# Camera_driver.net
KiCad netlist of a schematic drawn in EAGLE
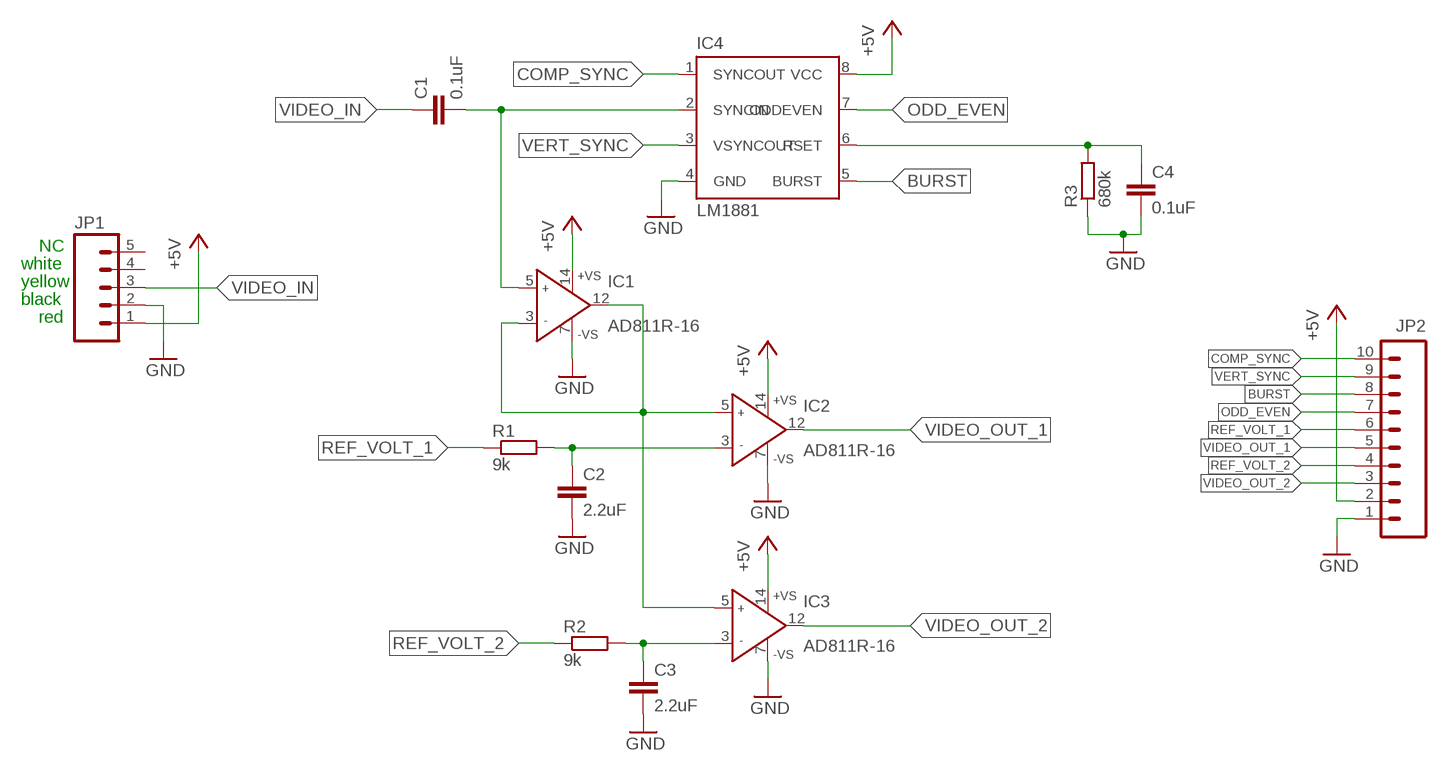
[diagram p0: schematic, sheet 1]

(export (version "E")
  (design (tool "Eeschema 10.0.6"))
  (components
    (comp (ref "C1")
      (value "0.1uF")
      (footprint "eagle-import:C0603")
      (libsource (lib "eagle-import") (part "C-EUC0603"))
    )
    (comp (ref "C2")
      (value "2.2uF")
      (footprint "eagle-import:C0603")
      (libsource (lib "eagle-import") (part "C-EUC0603"))
    )
    (comp (ref "C3")
      (value "2.2uF")
      (footprint "eagle-import:C0603")
      (libsource (lib "eagle-import") (part "C-EUC0603"))
    )
    (comp (ref "C4")
      (value "0.1uF")
      (footprint "eagle-import:C0603")
      (libsource (lib "eagle-import") (part "C-EUC0603"))
    )
    (comp (ref "IC1")
      (value "AD811R-16")
      (footprint "eagle-import:SOIC16R")
      (fields (field (name "MF") "ALTERA CORPORATION") (field (name "MPN") "AD811ARZ-16"))
      (libsource (lib "eagle-import") (part "AD811R-16"))
    )
    (comp (ref "IC2")
      (value "AD811R-16")
      (footprint "eagle-import:SOIC16R")
      (fields (field (name "MF") "ALTERA CORPORATION") (field (name "MPN") "AD811ARZ-16"))
      (libsource (lib "eagle-import") (part "AD811R-16"))
    )
    (comp (ref "IC3")
      (value "AD811R-16")
      (footprint "eagle-import:SOIC16R")
      (fields (field (name "MF") "ALTERA CORPORATION") (field (name "MPN") "AD811ARZ-16"))
      (libsource (lib "eagle-import") (part "AD811R-16"))
    )
    (comp (ref "IC4")
      (value "LM1881")
      (footprint "eagle-import:DIL08")
      (libsource (lib "eagle-import") (part "LM1881"))
    )
    (comp (ref "JP1")
      (value "M05PTH")
      (footprint "eagle-import:1X05")
      (libsource (lib "eagle-import") (part "M05PTH"))
    )
    (comp (ref "JP2")
      (value "M10SILK_FEMALE_PTH")
      (footprint "eagle-import:1X10")
      (libsource (lib "eagle-import") (part "M10SILK_FEMALE_PTH"))
    )
    (comp (ref "R1")
      (value "9k")
      (footprint "eagle-import:R0603")
      (libsource (lib "eagle-import") (part "R-EU_R0603"))
    )
    (comp (ref "R2")
      (value "9k")
      (footprint "eagle-import:R0603")
      (libsource (lib "eagle-import") (part "R-EU_R0603"))
    )
    (comp (ref "R3")
      (value "680k")
      (footprint "eagle-import:R0603")
      (libsource (lib "eagle-import") (part "R-EU_R0603"))
    )
  )
  (nets
    (net (code "1") (name "+5V") (class "Default")
      (node (ref "IC1") (pin "14") (pinfunction "+VS_14") (pintype "input"))
      (node (ref "IC2") (pin "14") (pinfunction "+VS_14") (pintype "input"))
      (node (ref "IC3") (pin "14") (pinfunction "+VS_14") (pintype "input"))
      (node (ref "IC4") (pin "8") (pinfunction "VCC_8") (pintype "power_in"))
      (node (ref "JP1") (pin "1") (pinfunction "1_1") (pintype "passive"))
      (node (ref "JP2") (pin "2") (pinfunction "2_2") (pintype "passive"))
    )
    (net (code "2") (name "BURST") (class "Default")
      (node (ref "IC4") (pin "5") (pinfunction "BURST_5") (pintype "output"))
      (node (ref "JP2") (pin "8") (pinfunction "8_8") (pintype "passive"))
    )
    (net (code "3") (name "COMP_SYNC") (class "Default")
      (node (ref "IC4") (pin "1") (pinfunction "SYNCOUT_1") (pintype "output"))
      (node (ref "JP2") (pin "10") (pinfunction "10_10") (pintype "passive"))
    )
    (net (code "4") (name "GND") (class "Default")
      (node (ref "C2") (pin "2") (pinfunction "2_2") (pintype "passive"))
      (node (ref "C3") (pin "2") (pinfunction "2_2") (pintype "passive"))
      (node (ref "C4") (pin "2") (pinfunction "2_2") (pintype "passive"))
      (node (ref "IC1") (pin "7") (pinfunction "-VS_7") (pintype "input"))
      (node (ref "IC2") (pin "7") (pinfunction "-VS_7") (pintype "input"))
      (node (ref "IC3") (pin "7") (pinfunction "-VS_7") (pintype "input"))
      (node (ref "IC4") (pin "4") (pinfunction "GND_4") (pintype "power_in"))
      (node (ref "JP1") (pin "2") (pinfunction "2_2") (pintype "passive"))
      (node (ref "JP2") (pin "1") (pinfunction "1_1") (pintype "passive"))
      (node (ref "R3") (pin "1") (pinfunction "1_1") (pintype "passive"))
    )
    (net (code "5") (name "Net-(IC1-IN+)") (class "Default")
      (node (ref "C1") (pin "2") (pinfunction "2_2") (pintype "passive"))
      (node (ref "IC1") (pin "5") (pinfunction "IN+_5") (pintype "input"))
      (node (ref "IC4") (pin "2") (pinfunction "SYNCIN_2") (pintype "input"))
    )
    (net (code "6") (name "Net-(IC1-IN-)") (class "Default")
      (node (ref "IC1") (pin "12") (pinfunction "OUT_12") (pintype "output"))
      (node (ref "IC1") (pin "3") (pinfunction "IN-_3") (pintype "input"))
      (node (ref "IC2") (pin "5") (pinfunction "IN+_5") (pintype "input"))
      (node (ref "IC3") (pin "5") (pinfunction "IN+_5") (pintype "input"))
    )
    (net (code "7") (name "Net-(IC2-IN-)") (class "Default")
      (node (ref "C2") (pin "1") (pinfunction "1_1") (pintype "passive"))
      (node (ref "IC2") (pin "3") (pinfunction "IN-_3") (pintype "input"))
      (node (ref "R1") (pin "2") (pinfunction "2_2") (pintype "passive"))
    )
    (net (code "8") (name "Net-(IC3-IN-)") (class "Default")
      (node (ref "C3") (pin "1") (pinfunction "1_1") (pintype "passive"))
      (node (ref "IC3") (pin "3") (pinfunction "IN-_3") (pintype "input"))
      (node (ref "R2") (pin "2") (pinfunction "2_2") (pintype "passive"))
    )
    (net (code "9") (name "Net-(IC4-RSET)") (class "Default")
      (node (ref "C4") (pin "1") (pinfunction "1_1") (pintype "passive"))
      (node (ref "IC4") (pin "6") (pinfunction "RSET_6") (pintype "output"))
      (node (ref "R3") (pin "2") (pinfunction "2_2") (pintype "passive"))
    )
    (net (code "10") (name "ODD_EVEN") (class "Default")
      (node (ref "IC4") (pin "7") (pinfunction "ODDEVEN_7") (pintype "output"))
      (node (ref "JP2") (pin "7") (pinfunction "7_7") (pintype "passive"))
    )
    (net (code "11") (name "REF_VOLT_1") (class "Default")
      (node (ref "JP2") (pin "6") (pinfunction "6_6") (pintype "passive"))
      (node (ref "R1") (pin "1") (pinfunction "1_1") (pintype "passive"))
    )
    (net (code "12") (name "REF_VOLT_2") (class "Default")
      (node (ref "JP2") (pin "4") (pinfunction "4_4") (pintype "passive"))
      (node (ref "R2") (pin "1") (pinfunction "1_1") (pintype "passive"))
    )
    (net (code "13") (name "VERT_SYNC") (class "Default")
      (node (ref "IC4") (pin "3") (pinfunction "VSYNCOUT_3") (pintype "output"))
      (node (ref "JP2") (pin "9") (pinfunction "9_9") (pintype "passive"))
    )
    (net (code "14") (name "VIDEO_IN") (class "Default")
      (node (ref "C1") (pin "1") (pinfunction "1_1") (pintype "passive"))
      (node (ref "JP1") (pin "3") (pinfunction "3_3") (pintype "passive"))
    )
    (net (code "15") (name "VIDEO_OUT_1") (class "Default")
      (node (ref "IC2") (pin "12") (pinfunction "OUT_12") (pintype "output"))
      (node (ref "JP2") (pin "5") (pinfunction "5_5") (pintype "passive"))
    )
    (net (code "16") (name "VIDEO_OUT_2") (class "Default")
      (node (ref "IC3") (pin "12") (pinfunction "OUT_12") (pintype "output"))
      (node (ref "JP2") (pin "3") (pinfunction "3_3") (pintype "passive"))
    )
    (net (code "17") (name "unconnected-(JP1-Pad4)") (class "Default")
      (node (ref "JP1") (pin "4") (pinfunction "4_4") (pintype "passive"))
    )
    (net (code "18") (name "unconnected-(JP1-Pad5)") (class "Default")
      (node (ref "JP1") (pin "5") (pinfunction "5_5") (pintype "passive"))
    )
  )
)
